# Digital_CPLD.net
KiCad netlist of a schematic drawn in Altium Designer
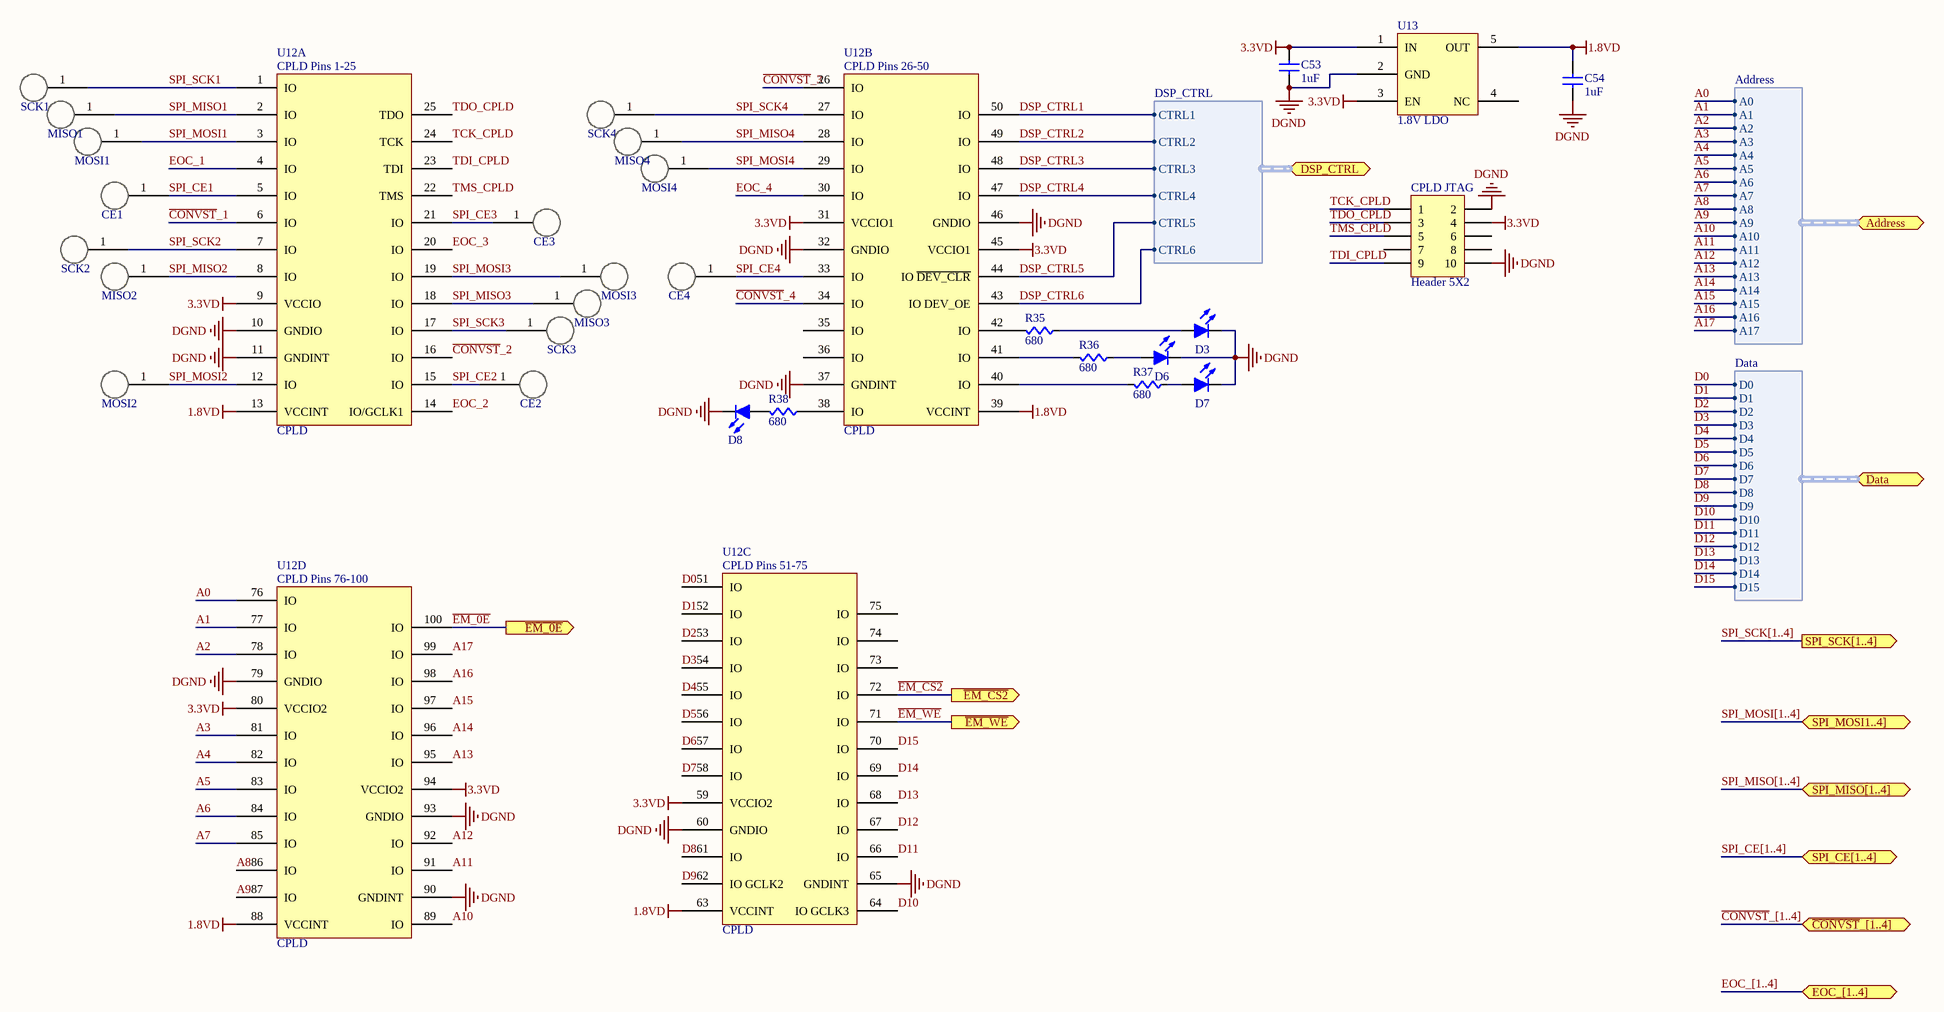
[diagram p0: Digital_CPLD.SchDoc]

(export (version "E")
  (design (tool "Eeschema 10.0.6"))
  (components
    (comp (ref "C53")
      (value "1uF")
      (footprint "CAPC0603")
      (fields (field (name "Comment") "Cap"))
      (libsource (lib "SubjuGator8") (part "Cap"))
    )
    (comp (ref "C54")
      (value "1uF")
      (footprint "CAPC0603")
      (fields (field (name "Comment") "Cap"))
      (libsource (lib "SubjuGator8") (part "Cap"))
    )
    (comp (ref "CE1")
      (value "Test_Point")
      (footprint "TP")
      (description "TEST POINT PC COMPACT .063\"D")
      (libsource (lib "Hydrophone") (part "Test_Point"))
    )
    (comp (ref "CE2")
      (value "Test_Point")
      (footprint "TP")
      (description "TEST POINT PC COMPACT .063\"D")
      (libsource (lib "Hydrophone") (part "Test_Point"))
    )
    (comp (ref "CE3")
      (value "Test_Point")
      (footprint "TP")
      (description "TEST POINT PC COMPACT .063\"D")
      (libsource (lib "Hydrophone") (part "Test_Point"))
    )
    (comp (ref "CE4")
      (value "Test_Point")
      (footprint "TP")
      (description "TEST POINT PC COMPACT .063\"D")
      (libsource (lib "Hydrophone") (part "Test_Point"))
    )
    (comp (ref "CPLD JTAG")
      (value "Header 5X2")
      (footprint "HDR2X5")
      (description "Header, 5-Pin, Dual row")
      (fields (field (name "PUBLISHER") "Altium Limited"))
      (libsource (lib "Miscellaneous Connectors") (part "Header 5X2"))
    )
    (comp (ref "D3")
      (value "LED-RED")
      (footprint "Hydrophone:LED0805-RED")
      (description "Light Emitting Diode - RED")
      (fields
        (field (name "MANUFACTURER PART NUMBER") "LTST-C171CKT")
        (field (name "MANUFACTURER") "Lite-On Inc")
      )
      (libsource (lib "Hydrophone") (part "LED-RED"))
    )
    (comp (ref "D6")
      (value "LED-RED")
      (footprint "Hydrophone:LED0805-RED")
      (description "Light Emitting Diode - RED")
      (fields
        (field (name "MANUFACTURER PART NUMBER") "LTST-C171CKT")
        (field (name "MANUFACTURER") "Lite-On Inc")
      )
      (libsource (lib "Hydrophone") (part "LED-RED"))
    )
    (comp (ref "D7")
      (value "LED-RED")
      (footprint "Hydrophone:LED0805-RED")
      (description "Light Emitting Diode - RED")
      (fields
        (field (name "MANUFACTURER PART NUMBER") "LTST-C171CKT")
        (field (name "MANUFACTURER") "Lite-On Inc")
      )
      (libsource (lib "Hydrophone") (part "LED-RED"))
    )
    (comp (ref "D8")
      (value "LED-RED")
      (footprint "Hydrophone:LED0805-RED")
      (description "Light Emitting Diode - RED")
      (fields
        (field (name "MANUFACTURER PART NUMBER") "LTST-C171CKT")
        (field (name "MANUFACTURER") "Lite-On Inc")
      )
      (libsource (lib "Hydrophone") (part "LED-RED"))
    )
    (comp (ref "MISO1")
      (value "Test_Point")
      (footprint "TP")
      (description "TEST POINT PC COMPACT .063\"D")
      (libsource (lib "Hydrophone") (part "Test_Point"))
    )
    (comp (ref "MISO2")
      (value "Test_Point")
      (footprint "TP")
      (description "TEST POINT PC COMPACT .063\"D")
      (libsource (lib "Hydrophone") (part "Test_Point"))
    )
    (comp (ref "MISO3")
      (value "Test_Point")
      (footprint "TP")
      (description "TEST POINT PC COMPACT .063\"D")
      (libsource (lib "Hydrophone") (part "Test_Point"))
    )
    (comp (ref "MISO4")
      (value "Test_Point")
      (footprint "TP")
      (description "TEST POINT PC COMPACT .063\"D")
      (libsource (lib "Hydrophone") (part "Test_Point"))
    )
    (comp (ref "MOSI1")
      (value "Test_Point")
      (footprint "TP")
      (description "TEST POINT PC COMPACT .063\"D")
      (libsource (lib "Hydrophone") (part "Test_Point"))
    )
    (comp (ref "MOSI2")
      (value "Test_Point")
      (footprint "TP")
      (description "TEST POINT PC COMPACT .063\"D")
      (libsource (lib "Hydrophone") (part "Test_Point"))
    )
    (comp (ref "MOSI3")
      (value "Test_Point")
      (footprint "TP")
      (description "TEST POINT PC COMPACT .063\"D")
      (libsource (lib "Hydrophone") (part "Test_Point"))
    )
    (comp (ref "MOSI4")
      (value "Test_Point")
      (footprint "TP")
      (description "TEST POINT PC COMPACT .063\"D")
      (libsource (lib "Hydrophone") (part "Test_Point"))
    )
    (comp (ref "R35")
      (value "680")
      (footprint "RES0603")
      (fields (field (name "Comment") "Res"))
      (libsource (lib "SubjuGator8") (part "Res"))
    )
    (comp (ref "R36")
      (value "680")
      (footprint "RES0603")
      (fields (field (name "Comment") "Res"))
      (libsource (lib "SubjuGator8") (part "Res"))
    )
    (comp (ref "R37")
      (value "680")
      (footprint "RES0603")
      (fields (field (name "Comment") "Res"))
      (libsource (lib "SubjuGator8") (part "Res"))
    )
    (comp (ref "R38")
      (value "680")
      (footprint "RES0603")
      (fields (field (name "Comment") "Res"))
      (libsource (lib "SubjuGator8") (part "Res"))
    )
    (comp (ref "SCK1")
      (value "Test_Point")
      (footprint "TP")
      (description "TEST POINT PC COMPACT .063\"D")
      (libsource (lib "Hydrophone") (part "Test_Point"))
    )
    (comp (ref "SCK2")
      (value "Test_Point")
      (footprint "TP")
      (description "TEST POINT PC COMPACT .063\"D")
      (libsource (lib "Hydrophone") (part "Test_Point"))
    )
    (comp (ref "SCK3")
      (value "Test_Point")
      (footprint "TP")
      (description "TEST POINT PC COMPACT .063\"D")
      (libsource (lib "Hydrophone") (part "Test_Point"))
    )
    (comp (ref "SCK4")
      (value "Test_Point")
      (footprint "TP")
      (description "TEST POINT PC COMPACT .063\"D")
      (libsource (lib "Hydrophone") (part "Test_Point"))
    )
    (comp (ref "U12")
      (value "CPLD")
      (footprint "TQFP-100")
      (description "IC CPLD 192MC 4.7NS 100TQFP")
      (libsource (lib "SubjuGator8") (part "EPM240GT100I5N"))
    )
    (comp (ref "U13")
      (value "1.8V LDO")
      (footprint "SOT23-5n")
      (description "IC REG LDO 1.8V 0.25A SOT23-5")
      (libsource (lib "SubjuGator8") (part "LP5907"))
    )
  )
  (nets
    (net (code "4") (name "/A0") (class "Default")
      (node (ref "U12") (pin "76") (pinfunction "IO_76") (pintype "passive"))
    )
    (net (code "5") (name "/A1") (class "Default")
      (node (ref "U12") (pin "77") (pinfunction "IO_77") (pintype "passive"))
    )
    (net (code "6") (name "/A2") (class "Default")
      (node (ref "U12") (pin "78") (pinfunction "IO_78") (pintype "passive"))
    )
    (net (code "7") (name "/A3") (class "Default")
      (node (ref "U12") (pin "81") (pinfunction "IO_81") (pintype "passive"))
    )
    (net (code "8") (name "/A4") (class "Default")
      (node (ref "U12") (pin "82") (pinfunction "IO_82") (pintype "passive"))
    )
    (net (code "9") (name "/A5") (class "Default")
      (node (ref "U12") (pin "83") (pinfunction "IO_83") (pintype "passive"))
    )
    (net (code "10") (name "/A6") (class "Default")
      (node (ref "U12") (pin "84") (pinfunction "IO_84") (pintype "passive"))
    )
    (net (code "11") (name "/A7") (class "Default")
      (node (ref "U12") (pin "85") (pinfunction "IO_85") (pintype "passive"))
    )
    (net (code "12") (name "/A8") (class "Default")
      (node (ref "U12") (pin "86") (pinfunction "IO_86") (pintype "passive"))
    )
    (net (code "13") (name "/A9") (class "Default")
      (node (ref "U12") (pin "87") (pinfunction "IO_87") (pintype "passive"))
    )
    (net (code "14") (name "/A10") (class "Default")
      (node (ref "U12") (pin "89") (pinfunction "IO_89") (pintype "passive"))
    )
    (net (code "15") (name "/A11") (class "Default")
      (node (ref "U12") (pin "91") (pinfunction "IO_91") (pintype "passive"))
    )
    (net (code "16") (name "/A12") (class "Default")
      (node (ref "U12") (pin "92") (pinfunction "IO_92") (pintype "passive"))
    )
    (net (code "17") (name "/A13") (class "Default")
      (node (ref "U12") (pin "95") (pinfunction "IO_95") (pintype "passive"))
    )
    (net (code "18") (name "/A14") (class "Default")
      (node (ref "U12") (pin "96") (pinfunction "IO_96") (pintype "passive"))
    )
    (net (code "19") (name "/A15") (class "Default")
      (node (ref "U12") (pin "97") (pinfunction "IO_97") (pintype "passive"))
    )
    (net (code "20") (name "/A16") (class "Default")
      (node (ref "U12") (pin "98") (pinfunction "IO_98") (pintype "passive"))
    )
    (net (code "21") (name "/A17") (class "Default")
      (node (ref "U12") (pin "99") (pinfunction "IO_99") (pintype "passive"))
    )
    (net (code "22") (name "/D0") (class "Default")
      (node (ref "U12") (pin "51") (pinfunction "IO_51") (pintype "passive"))
    )
    (net (code "23") (name "/D1") (class "Default")
      (node (ref "U12") (pin "52") (pinfunction "IO_52") (pintype "passive"))
    )
    (net (code "24") (name "/D2") (class "Default")
      (node (ref "U12") (pin "53") (pinfunction "IO_53") (pintype "passive"))
    )
    (net (code "25") (name "/D3") (class "Default")
      (node (ref "U12") (pin "54") (pinfunction "IO_54") (pintype "passive"))
    )
    (net (code "26") (name "/D4") (class "Default")
      (node (ref "U12") (pin "55") (pinfunction "IO_55") (pintype "passive"))
    )
    (net (code "27") (name "/D5") (class "Default")
      (node (ref "U12") (pin "56") (pinfunction "IO_56") (pintype "passive"))
    )
    (net (code "28") (name "/D6") (class "Default")
      (node (ref "U12") (pin "57") (pinfunction "IO_57") (pintype "passive"))
    )
    (net (code "29") (name "/D7") (class "Default")
      (node (ref "U12") (pin "58") (pinfunction "IO_58") (pintype "passive"))
    )
    (net (code "30") (name "/D8") (class "Default")
      (node (ref "U12") (pin "61") (pinfunction "IO_61") (pintype "passive"))
    )
    (net (code "31") (name "/D9") (class "Default")
      (node (ref "U12") (pin "62") (pinfunction "IO_GCLK2_62") (pintype "passive"))
    )
    (net (code "32") (name "/D10") (class "Default")
      (node (ref "U12") (pin "64") (pinfunction "IO_GCLK3_64") (pintype "passive"))
    )
    (net (code "33") (name "/D11") (class "Default")
      (node (ref "U12") (pin "66") (pinfunction "IO_66") (pintype "passive"))
    )
    (net (code "34") (name "/D12") (class "Default")
      (node (ref "U12") (pin "67") (pinfunction "IO_67") (pintype "passive"))
    )
    (net (code "35") (name "/D13") (class "Default")
      (node (ref "U12") (pin "68") (pinfunction "IO_68") (pintype "passive"))
    )
    (net (code "36") (name "/D14") (class "Default")
      (node (ref "U12") (pin "69") (pinfunction "IO_69") (pintype "passive"))
    )
    (net (code "37") (name "/D15") (class "Default")
      (node (ref "U12") (pin "70") (pinfunction "IO_70") (pintype "passive"))
    )
    (net (code "38") (name "/DSP_CTRL1") (class "Default")
      (node (ref "U12") (pin "50") (pinfunction "IO_50") (pintype "passive"))
    )
    (net (code "39") (name "/DSP_CTRL2") (class "Default")
      (node (ref "U12") (pin "49") (pinfunction "IO_49") (pintype "passive"))
    )
    (net (code "40") (name "/DSP_CTRL3") (class "Default")
      (node (ref "U12") (pin "48") (pinfunction "IO_48") (pintype "passive"))
    )
    (net (code "41") (name "/DSP_CTRL4") (class "Default")
      (node (ref "U12") (pin "47") (pinfunction "IO_47") (pintype "passive"))
    )
    (net (code "42") (name "/DSP_CTRL5") (class "Default")
      (node (ref "U12") (pin "44") (pinfunction "IO_~{DEV_CLR}_44") (pintype "passive"))
    )
    (net (code "43") (name "/DSP_CTRL6") (class "Default")
      (node (ref "U12") (pin "43") (pinfunction "IO_DEV_OE_43") (pintype "passive"))
    )
    (net (code "44") (name "/EOC_1") (class "Default")
      (node (ref "U12") (pin "4") (pinfunction "IO_4") (pintype "passive"))
    )
    (net (code "45") (name "/EOC_2") (class "Default")
      (node (ref "U12") (pin "14") (pinfunction "IO/GCLK1_14") (pintype "passive"))
    )
    (net (code "46") (name "/EOC_3") (class "Default")
      (node (ref "U12") (pin "20") (pinfunction "IO_20") (pintype "passive"))
    )
    (net (code "47") (name "/EOC_4") (class "Default")
      (node (ref "U12") (pin "30") (pinfunction "IO_30") (pintype "passive"))
    )
    (net (code "49") (name "/SPI_CE1") (class "Default")
      (node (ref "CE1") (pin "1") (pintype "passive"))
      (node (ref "U12") (pin "5") (pinfunction "IO_5") (pintype "passive"))
    )
    (net (code "50") (name "/SPI_CE2") (class "Default")
      (node (ref "CE2") (pin "1") (pintype "passive"))
      (node (ref "U12") (pin "15") (pinfunction "IO_15") (pintype "passive"))
    )
    (net (code "51") (name "/SPI_CE3") (class "Default")
      (node (ref "CE3") (pin "1") (pintype "passive"))
      (node (ref "U12") (pin "21") (pinfunction "IO_21") (pintype "passive"))
    )
    (net (code "52") (name "/SPI_CE4") (class "Default")
      (node (ref "CE4") (pin "1") (pintype "passive"))
      (node (ref "U12") (pin "33") (pinfunction "IO_33") (pintype "passive"))
    )
    (net (code "54") (name "/SPI_MISO1") (class "Default")
      (node (ref "MISO1") (pin "1") (pintype "passive"))
      (node (ref "U12") (pin "2") (pinfunction "IO_2") (pintype "passive"))
    )
    (net (code "55") (name "/SPI_MISO2") (class "Default")
      (node (ref "MISO2") (pin "1") (pintype "passive"))
      (node (ref "U12") (pin "8") (pinfunction "IO_8") (pintype "passive"))
    )
    (net (code "56") (name "/SPI_MISO3") (class "Default")
      (node (ref "MISO3") (pin "1") (pintype "passive"))
      (node (ref "U12") (pin "18") (pinfunction "IO_18") (pintype "passive"))
    )
    (net (code "57") (name "/SPI_MISO4") (class "Default")
      (node (ref "MISO4") (pin "1") (pintype "passive"))
      (node (ref "U12") (pin "28") (pinfunction "IO_28") (pintype "passive"))
    )
    (net (code "59") (name "/SPI_MOSI1") (class "Default")
      (node (ref "MOSI1") (pin "1") (pintype "passive"))
      (node (ref "U12") (pin "3") (pinfunction "IO_3") (pintype "passive"))
    )
    (net (code "60") (name "/SPI_MOSI2") (class "Default")
      (node (ref "MOSI2") (pin "1") (pintype "passive"))
      (node (ref "U12") (pin "12") (pinfunction "IO_12") (pintype "passive"))
    )
    (net (code "61") (name "/SPI_MOSI3") (class "Default")
      (node (ref "MOSI3") (pin "1") (pintype "passive"))
      (node (ref "U12") (pin "19") (pinfunction "IO_19") (pintype "passive"))
    )
    (net (code "62") (name "/SPI_MOSI4") (class "Default")
      (node (ref "MOSI4") (pin "1") (pintype "passive"))
      (node (ref "U12") (pin "29") (pinfunction "IO_29") (pintype "passive"))
    )
    (net (code "64") (name "/SPI_SCK1") (class "Default")
      (node (ref "SCK1") (pin "1") (pintype "passive"))
      (node (ref "U12") (pin "1") (pinfunction "IO_1") (pintype "passive"))
    )
    (net (code "65") (name "/SPI_SCK2") (class "Default")
      (node (ref "SCK2") (pin "1") (pintype "passive"))
      (node (ref "U12") (pin "7") (pinfunction "IO_7") (pintype "passive"))
    )
    (net (code "66") (name "/SPI_SCK3") (class "Default")
      (node (ref "SCK3") (pin "1") (pintype "passive"))
      (node (ref "U12") (pin "17") (pinfunction "IO_17") (pintype "passive"))
    )
    (net (code "67") (name "/SPI_SCK4") (class "Default")
      (node (ref "SCK4") (pin "1") (pintype "passive"))
      (node (ref "U12") (pin "27") (pinfunction "IO_27") (pintype "passive"))
    )
    (net (code "69") (name "/TCK_CPLD") (class "Default")
      (node (ref "CPLD JTAG") (pin "1") (pinfunction "1_1") (pintype "passive"))
      (node (ref "U12") (pin "24") (pinfunction "TCK_24") (pintype "passive"))
    )
    (net (code "70") (name "/TDI_CPLD") (class "Default")
      (node (ref "CPLD JTAG") (pin "9") (pinfunction "9_9") (pintype "passive"))
      (node (ref "U12") (pin "23") (pinfunction "TDI_23") (pintype "passive"))
    )
    (net (code "71") (name "/TDO_CPLD") (class "Default")
      (node (ref "CPLD JTAG") (pin "3") (pinfunction "3_3") (pintype "passive"))
      (node (ref "U12") (pin "25") (pinfunction "TDO_25") (pintype "passive"))
    )
    (net (code "72") (name "/TMS_CPLD") (class "Default")
      (node (ref "CPLD JTAG") (pin "5") (pinfunction "5_5") (pintype "passive"))
      (node (ref "U12") (pin "22") (pinfunction "TMS_22") (pintype "passive"))
    )
    (net (code "76") (name "/~{CONVST}_1") (class "Default")
      (node (ref "U12") (pin "6") (pinfunction "IO_6") (pintype "passive"))
    )
    (net (code "77") (name "/~{CONVST}_2") (class "Default")
      (node (ref "U12") (pin "16") (pinfunction "IO_16") (pintype "passive"))
    )
    (net (code "78") (name "/~{CONVST}_3") (class "Default")
      (node (ref "U12") (pin "26") (pinfunction "IO_26") (pintype "passive"))
    )
    (net (code "79") (name "/~{CONVST}_4") (class "Default")
      (node (ref "U12") (pin "34") (pinfunction "IO_34") (pintype "passive"))
    )
    (net (code "81") (name "/~{EM_0E}") (class "Default")
      (node (ref "U12") (pin "100") (pinfunction "IO_100") (pintype "passive"))
    )
    (net (code "82") (name "/~{EM_CS2}") (class "Default")
      (node (ref "U12") (pin "72") (pinfunction "IO_72") (pintype "passive"))
    )
    (net (code "83") (name "/~{EM_WE}") (class "Default")
      (node (ref "U12") (pin "71") (pinfunction "IO_71") (pintype "passive"))
    )
    (net (code "84") (name "1.8VD") (class "Default")
      (node (ref "C54") (pin "1") (pinfunction "A_1") (pintype "passive"))
      (node (ref "U12") (pin "13") (pinfunction "VCCINT_13") (pintype "passive"))
      (node (ref "U12") (pin "39") (pinfunction "VCCINT_39") (pintype "passive"))
      (node (ref "U12") (pin "63") (pinfunction "VCCINT_63") (pintype "passive"))
      (node (ref "U12") (pin "88") (pinfunction "VCCINT_88") (pintype "passive"))
      (node (ref "U13") (pin "5") (pinfunction "OUT_5") (pintype "passive"))
    )
    (net (code "85") (name "3.3VD") (class "Default")
      (node (ref "C53") (pin "1") (pinfunction "A_1") (pintype "passive"))
      (node (ref "CPLD JTAG") (pin "4") (pinfunction "4_4") (pintype "passive"))
      (node (ref "U12") (pin "31") (pinfunction "VCCIO1_31") (pintype "passive"))
      (node (ref "U12") (pin "45") (pinfunction "VCCIO1_45") (pintype "passive"))
      (node (ref "U12") (pin "59") (pinfunction "VCCIO2_59") (pintype "passive"))
      (node (ref "U12") (pin "80") (pinfunction "VCCIO2_80") (pintype "passive"))
      (node (ref "U12") (pin "9") (pinfunction "VCCIO_9") (pintype "passive"))
      (node (ref "U12") (pin "94") (pinfunction "VCCIO2_94") (pintype "passive"))
      (node (ref "U13") (pin "1") (pinfunction "IN_1") (pintype "passive"))
      (node (ref "U13") (pin "3") (pinfunction "EN_3") (pintype "passive"))
    )
    (net (code "86") (name "DGND") (class "Default")
      (node (ref "C53") (pin "2") (pinfunction "B_2") (pintype "passive"))
      (node (ref "C54") (pin "2") (pinfunction "B_2") (pintype "passive"))
      (node (ref "CPLD JTAG") (pin "10") (pinfunction "10_10") (pintype "passive"))
      (node (ref "CPLD JTAG") (pin "2") (pinfunction "2_2") (pintype "passive"))
      (node (ref "D3") (pin "1") (pinfunction "K_1") (pintype "passive"))
      (node (ref "D6") (pin "1") (pinfunction "K_1") (pintype "passive"))
      (node (ref "D7") (pin "1") (pinfunction "K_1") (pintype "passive"))
      (node (ref "D8") (pin "1") (pinfunction "K_1") (pintype "passive"))
      (node (ref "U12") (pin "10") (pinfunction "GNDIO_10") (pintype "passive"))
      (node (ref "U12") (pin "11") (pinfunction "GNDINT_11") (pintype "passive"))
      (node (ref "U12") (pin "32") (pinfunction "GNDIO_32") (pintype "passive"))
      (node (ref "U12") (pin "37") (pinfunction "GNDINT_37") (pintype "passive"))
      (node (ref "U12") (pin "46") (pinfunction "GNDIO_46") (pintype "passive"))
      (node (ref "U12") (pin "60") (pinfunction "GNDIO_60") (pintype "passive"))
      (node (ref "U12") (pin "65") (pinfunction "GNDINT_65") (pintype "passive"))
      (node (ref "U12") (pin "79") (pinfunction "GNDIO_79") (pintype "passive"))
      (node (ref "U12") (pin "90") (pinfunction "GNDINT_90") (pintype "passive"))
      (node (ref "U12") (pin "93") (pinfunction "GNDIO_93") (pintype "passive"))
      (node (ref "U13") (pin "2") (pinfunction "GND_2") (pintype "passive"))
    )
    (net (code "87") (name "Net-(D3-A)") (class "Default")
      (node (ref "D3") (pin "2") (pinfunction "A_2") (pintype "passive"))
      (node (ref "R35") (pin "2") (pinfunction "B_2") (pintype "passive"))
    )
    (net (code "88") (name "Net-(D6-A)") (class "Default")
      (node (ref "D6") (pin "2") (pinfunction "A_2") (pintype "passive"))
      (node (ref "R36") (pin "2") (pinfunction "B_2") (pintype "passive"))
    )
    (net (code "89") (name "Net-(D7-A)") (class "Default")
      (node (ref "D7") (pin "2") (pinfunction "A_2") (pintype "passive"))
      (node (ref "R37") (pin "2") (pinfunction "B_2") (pintype "passive"))
    )
    (net (code "90") (name "Net-(D8-A)") (class "Default")
      (node (ref "D8") (pin "2") (pinfunction "A_2") (pintype "passive"))
      (node (ref "R38") (pin "1") (pinfunction "A_1") (pintype "passive"))
    )
    (net (code "91") (name "Net-(R35-A)") (class "Default")
      (node (ref "R35") (pin "1") (pinfunction "A_1") (pintype "passive"))
      (node (ref "U12") (pin "42") (pinfunction "IO_42") (pintype "passive"))
    )
    (net (code "92") (name "Net-(R36-A)") (class "Default")
      (node (ref "R36") (pin "1") (pinfunction "A_1") (pintype "passive"))
      (node (ref "U12") (pin "41") (pinfunction "IO_41") (pintype "passive"))
    )
    (net (code "93") (name "Net-(R37-A)") (class "Default")
      (node (ref "R37") (pin "1") (pinfunction "A_1") (pintype "passive"))
      (node (ref "U12") (pin "40") (pinfunction "IO_40") (pintype "passive"))
    )
    (net (code "94") (name "Net-(R38-B)") (class "Default")
      (node (ref "R38") (pin "2") (pinfunction "B_2") (pintype "passive"))
      (node (ref "U12") (pin "38") (pinfunction "IO_38") (pintype "passive"))
    )
    (net (code "95") (name "unconnected-(CPLD JTAG-Pad6)") (class "Default")
      (node (ref "CPLD JTAG") (pin "6") (pinfunction "6_6") (pintype "passive"))
    )
    (net (code "96") (name "unconnected-(CPLD JTAG-Pad7)") (class "Default")
      (node (ref "CPLD JTAG") (pin "7") (pinfunction "7_7") (pintype "passive"))
    )
    (net (code "97") (name "unconnected-(CPLD JTAG-Pad8)") (class "Default")
      (node (ref "CPLD JTAG") (pin "8") (pinfunction "8_8") (pintype "passive"))
    )
    (net (code "98") (name "unconnected-(U12B-IO-Pad35)") (class "Default")
      (node (ref "U12") (pin "35") (pinfunction "IO_35") (pintype "passive"))
    )
    (net (code "99") (name "unconnected-(U12B-IO-Pad36)") (class "Default")
      (node (ref "U12") (pin "36") (pinfunction "IO_36") (pintype "passive"))
    )
    (net (code "100") (name "unconnected-(U12C-IO-Pad73)") (class "Default")
      (node (ref "U12") (pin "73") (pinfunction "IO_73") (pintype "passive"))
    )
    (net (code "101") (name "unconnected-(U12C-IO-Pad74)") (class "Default")
      (node (ref "U12") (pin "74") (pinfunction "IO_74") (pintype "passive"))
    )
    (net (code "102") (name "unconnected-(U12C-IO-Pad75)") (class "Default")
      (node (ref "U12") (pin "75") (pinfunction "IO_75") (pintype "passive"))
    )
    (net (code "103") (name "unconnected-(U13-NC-Pad4)") (class "Default")
      (node (ref "U13") (pin "4") (pinfunction "NC_4") (pintype "passive"))
    )
  )
)
